# LilyPad_LED_v11a.net
KiCad netlist of a schematic drawn in EAGLE
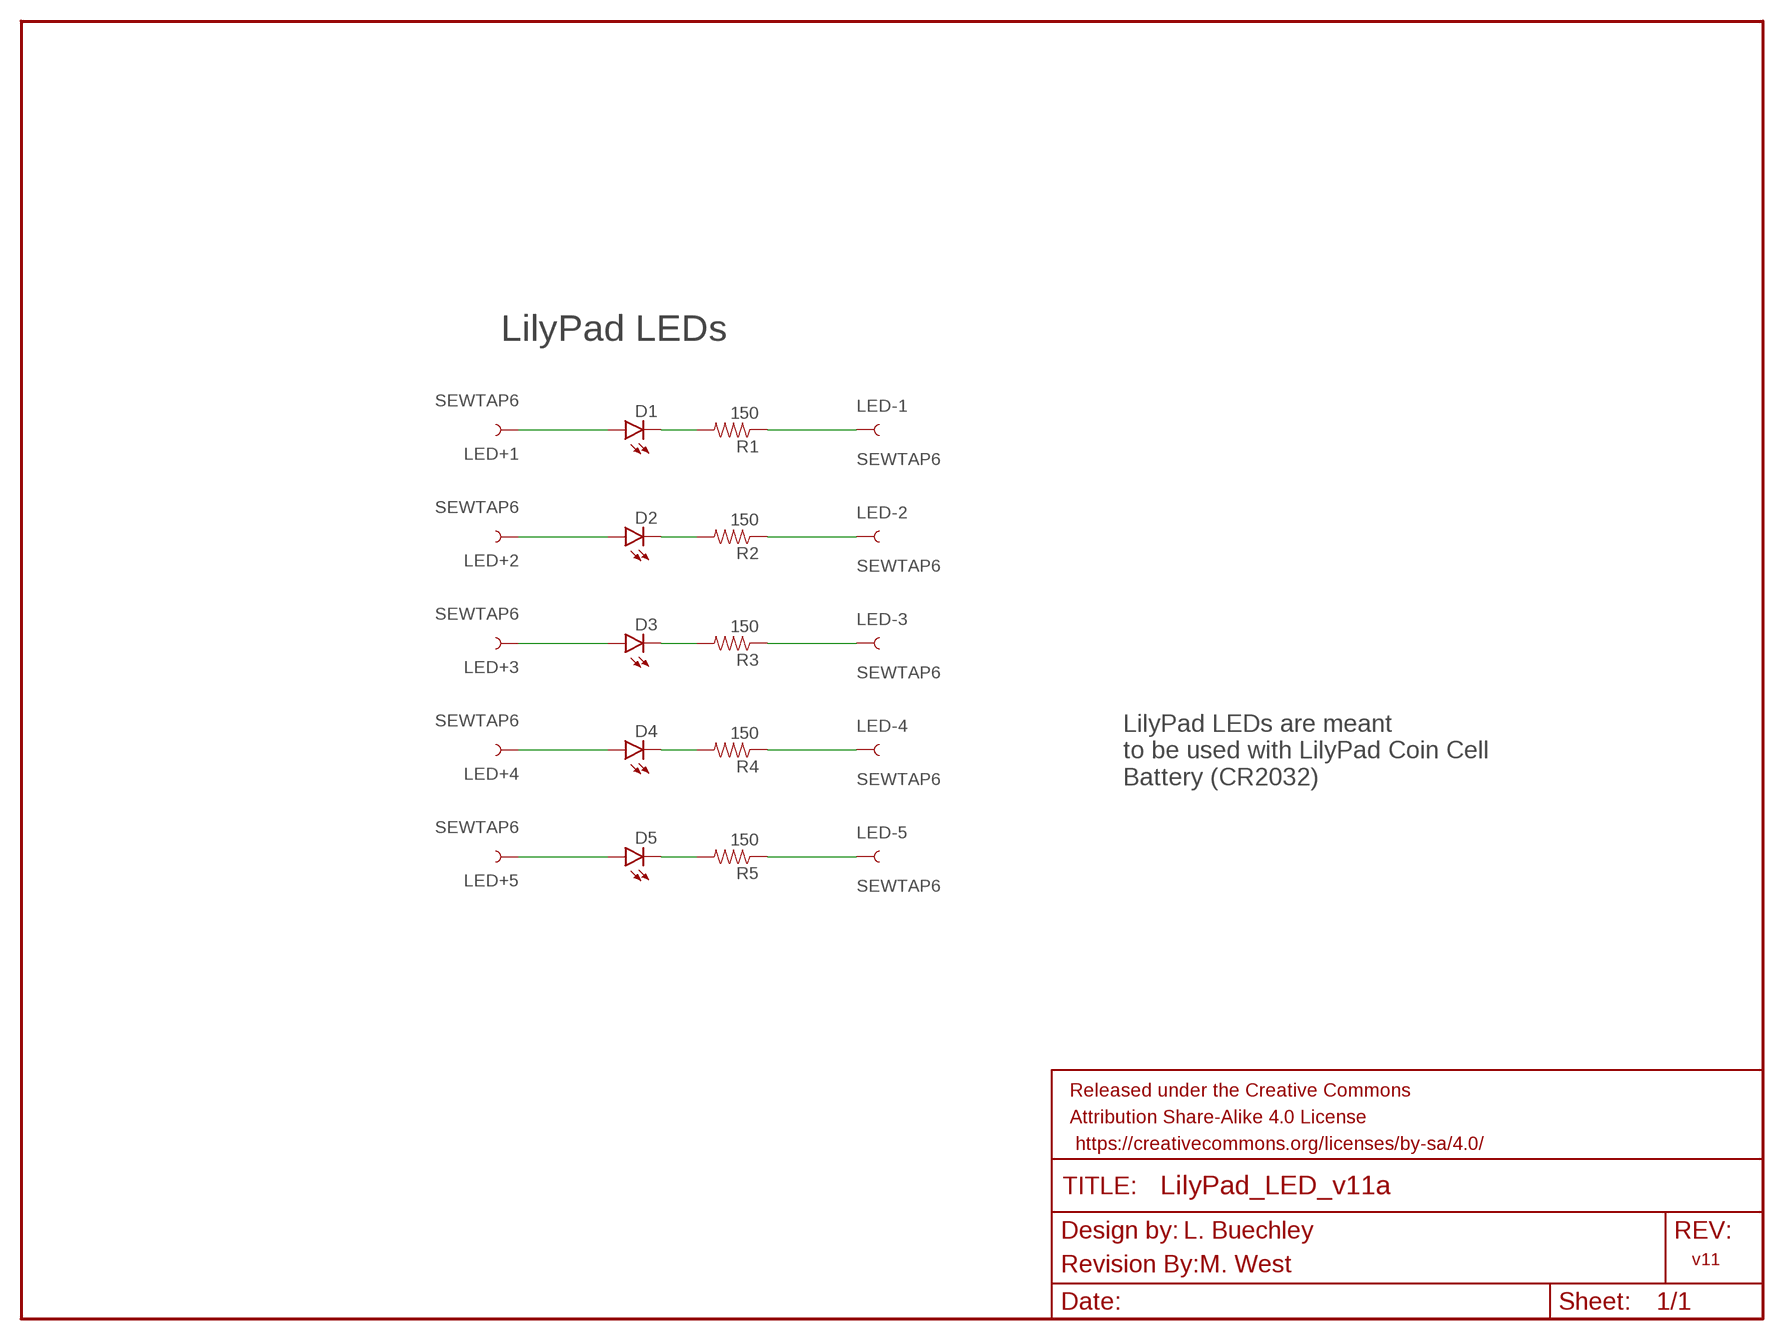
[diagram p0: schematic, sheet 1]

(export (version "E")
  (design (tool "Eeschema 10.0.6"))
  (components
    (comp (ref "D1")
      (value "LED-WHITE1206")
      (footprint "eagle-import:LED-1206")
      (libsource (lib "eagle-import") (part "LED-WHITE1206"))
    )
    (comp (ref "D2")
      (value "LED-WHITE1206")
      (footprint "eagle-import:LED-1206")
      (libsource (lib "eagle-import") (part "LED-WHITE1206"))
    )
    (comp (ref "D3")
      (value "LED-WHITE1206")
      (footprint "eagle-import:LED-1206")
      (libsource (lib "eagle-import") (part "LED-WHITE1206"))
    )
    (comp (ref "D4")
      (value "LED-WHITE1206")
      (footprint "eagle-import:LED-1206")
      (libsource (lib "eagle-import") (part "LED-WHITE1206"))
    )
    (comp (ref "D5")
      (value "LED-WHITE1206")
      (footprint "eagle-import:LED-1206")
      (libsource (lib "eagle-import") (part "LED-WHITE1206"))
    )
    (comp (ref "FRAME1")
      (value "FRAME-LETTER")
      (footprint "eagle-import:CREATIVE_COMMONS")
      (libsource (lib "eagle-import") (part "FRAME-LETTER"))
    )
    (comp (ref "LED+1")
      (value "SEWTAP6")
      (footprint "eagle-import:PETAL-SMALL-2SIDE")
      (libsource (lib "eagle-import") (part "SEWTAP6"))
    )
    (comp (ref "LED+2")
      (value "SEWTAP6")
      (footprint "eagle-import:PETAL-SMALL-2SIDE")
      (libsource (lib "eagle-import") (part "SEWTAP6"))
    )
    (comp (ref "LED+3")
      (value "SEWTAP6")
      (footprint "eagle-import:PETAL-SMALL-2SIDE")
      (libsource (lib "eagle-import") (part "SEWTAP6"))
    )
    (comp (ref "LED+4")
      (value "SEWTAP6")
      (footprint "eagle-import:PETAL-SMALL-2SIDE")
      (libsource (lib "eagle-import") (part "SEWTAP6"))
    )
    (comp (ref "LED+5")
      (value "SEWTAP6")
      (footprint "eagle-import:PETAL-SMALL-2SIDE")
      (libsource (lib "eagle-import") (part "SEWTAP6"))
    )
    (comp (ref "LED-1")
      (value "SEWTAP6")
      (footprint "eagle-import:PETAL-SMALL-2SIDE")
      (libsource (lib "eagle-import") (part "SEWTAP6"))
    )
    (comp (ref "LED-2")
      (value "SEWTAP6")
      (footprint "eagle-import:PETAL-SMALL-2SIDE")
      (libsource (lib "eagle-import") (part "SEWTAP6"))
    )
    (comp (ref "LED-3")
      (value "SEWTAP6")
      (footprint "eagle-import:PETAL-SMALL-2SIDE")
      (libsource (lib "eagle-import") (part "SEWTAP6"))
    )
    (comp (ref "LED-4")
      (value "SEWTAP6")
      (footprint "eagle-import:PETAL-SMALL-2SIDE")
      (libsource (lib "eagle-import") (part "SEWTAP6"))
    )
    (comp (ref "LED-5")
      (value "SEWTAP6")
      (footprint "eagle-import:PETAL-SMALL-2SIDE")
      (libsource (lib "eagle-import") (part "SEWTAP6"))
    )
    (comp (ref "R1")
      (value "150")
      (footprint "eagle-import:0603-RES")
      (libsource (lib "eagle-import") (part "150OHM-1/10W-1%(0603)"))
    )
    (comp (ref "R2")
      (value "150")
      (footprint "eagle-import:0603-RES")
      (libsource (lib "eagle-import") (part "150OHM-1/10W-1%(0603)"))
    )
    (comp (ref "R3")
      (value "150")
      (footprint "eagle-import:0603-RES")
      (libsource (lib "eagle-import") (part "150OHM-1/10W-1%(0603)"))
    )
    (comp (ref "R4")
      (value "150")
      (footprint "eagle-import:0603-RES")
      (libsource (lib "eagle-import") (part "150OHM-1/10W-1%(0603)"))
    )
    (comp (ref "R5")
      (value "150")
      (footprint "eagle-import:0603-RES")
      (libsource (lib "eagle-import") (part "150OHM-1/10W-1%(0603)"))
    )
    (comp (ref "U$6")
      (value "REVISION")
      (footprint "eagle-import:REVISION")
      (libsource (lib "eagle-import") (part "REVISION"))
    )
  )
  (nets
    (net (code "1") (name "Net-(D1-PadA)") (class "Default")
      (node (ref "D1") (pin "A") (pinfunction "A_A") (pintype "passive"))
      (node (ref "LED+1") (pin "1") (pinfunction "1_1") (pintype "bidirectional"))
    )
    (net (code "2") (name "Net-(D1-PadC)") (class "Default")
      (node (ref "D1") (pin "C") (pinfunction "C_C") (pintype "passive"))
      (node (ref "R1") (pin "2") (pinfunction "2_2") (pintype "passive"))
    )
    (net (code "3") (name "Net-(D2-PadA)") (class "Default")
      (node (ref "D2") (pin "A") (pinfunction "A_A") (pintype "passive"))
      (node (ref "LED+2") (pin "1") (pinfunction "1_1") (pintype "bidirectional"))
    )
    (net (code "4") (name "Net-(D2-PadC)") (class "Default")
      (node (ref "D2") (pin "C") (pinfunction "C_C") (pintype "passive"))
      (node (ref "R2") (pin "2") (pinfunction "2_2") (pintype "passive"))
    )
    (net (code "5") (name "Net-(D3-PadA)") (class "Default")
      (node (ref "D3") (pin "A") (pinfunction "A_A") (pintype "passive"))
      (node (ref "LED+3") (pin "1") (pinfunction "1_1") (pintype "bidirectional"))
    )
    (net (code "6") (name "Net-(D3-PadC)") (class "Default")
      (node (ref "D3") (pin "C") (pinfunction "C_C") (pintype "passive"))
      (node (ref "R3") (pin "2") (pinfunction "2_2") (pintype "passive"))
    )
    (net (code "7") (name "Net-(D4-PadA)") (class "Default")
      (node (ref "D4") (pin "A") (pinfunction "A_A") (pintype "passive"))
      (node (ref "LED+4") (pin "1") (pinfunction "1_1") (pintype "bidirectional"))
    )
    (net (code "8") (name "Net-(D4-PadC)") (class "Default")
      (node (ref "D4") (pin "C") (pinfunction "C_C") (pintype "passive"))
      (node (ref "R4") (pin "2") (pinfunction "2_2") (pintype "passive"))
    )
    (net (code "9") (name "Net-(D5-PadA)") (class "Default")
      (node (ref "D5") (pin "A") (pinfunction "A_A") (pintype "passive"))
      (node (ref "LED+5") (pin "1") (pinfunction "1_1") (pintype "bidirectional"))
    )
    (net (code "10") (name "Net-(D5-PadC)") (class "Default")
      (node (ref "D5") (pin "C") (pinfunction "C_C") (pintype "passive"))
      (node (ref "R5") (pin "2") (pinfunction "2_2") (pintype "passive"))
    )
    (net (code "11") (name "Net-(LED-1-Pad1)") (class "Default")
      (node (ref "LED-1") (pin "1") (pinfunction "1_1") (pintype "bidirectional"))
      (node (ref "R1") (pin "1") (pinfunction "1_1") (pintype "passive"))
    )
    (net (code "12") (name "Net-(LED-2-Pad1)") (class "Default")
      (node (ref "LED-2") (pin "1") (pinfunction "1_1") (pintype "bidirectional"))
      (node (ref "R2") (pin "1") (pinfunction "1_1") (pintype "passive"))
    )
    (net (code "13") (name "Net-(LED-3-Pad1)") (class "Default")
      (node (ref "LED-3") (pin "1") (pinfunction "1_1") (pintype "bidirectional"))
      (node (ref "R3") (pin "1") (pinfunction "1_1") (pintype "passive"))
    )
    (net (code "14") (name "Net-(LED-4-Pad1)") (class "Default")
      (node (ref "LED-4") (pin "1") (pinfunction "1_1") (pintype "bidirectional"))
      (node (ref "R4") (pin "1") (pinfunction "1_1") (pintype "passive"))
    )
    (net (code "15") (name "Net-(LED-5-Pad1)") (class "Default")
      (node (ref "LED-5") (pin "1") (pinfunction "1_1") (pintype "bidirectional"))
      (node (ref "R5") (pin "1") (pinfunction "1_1") (pintype "passive"))
    )
  )
)
